# GRLV_double_Rail_v0_2b_P1.net
KiCad netlist of a schematic drawn in Altium Designer
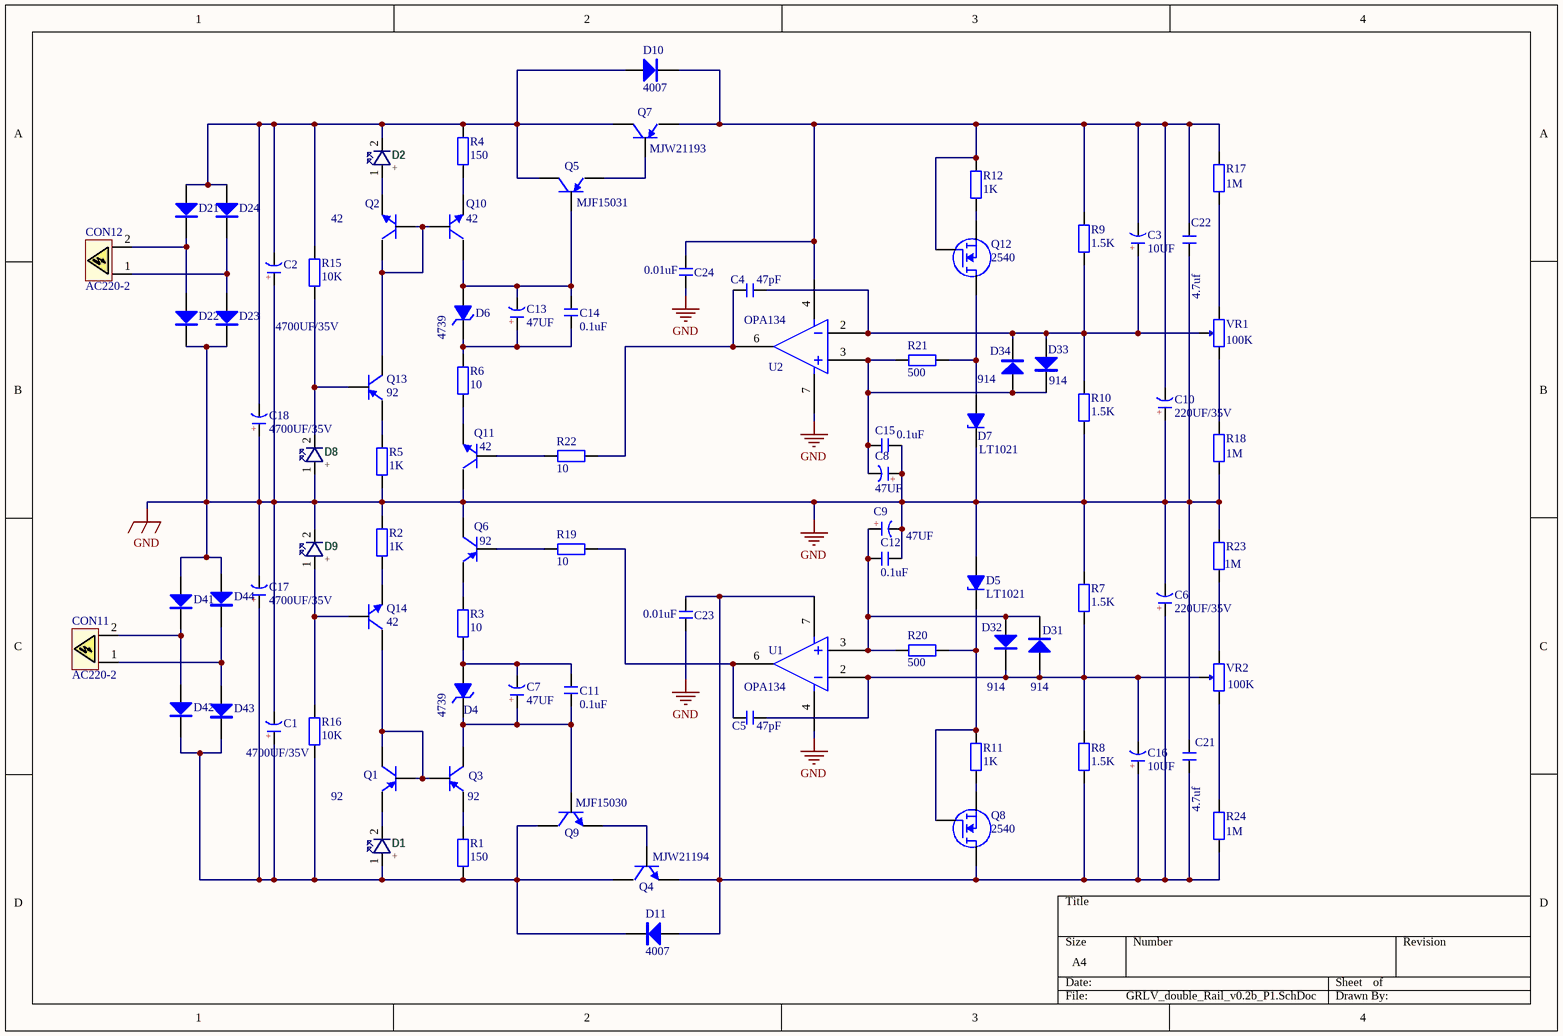
[diagram p0: GRLV_double_Rail_v0.2b_P1.SchDoc]

(export (version "E")
  (design (tool "Eeschema 10.0.6"))
  (components
    (comp (ref "C1")
      (value "4700UF/35V")
      (footprint "CAP 10*22*31.5")
      (description "直插电解电容")
      (fields (field (name "版权归属") "源创客"))
      (libsource (lib "") (part "C-CAP_1"))
    )
    (comp (ref "C2")
      (value "4700UF/35V")
      (footprint "CAP 10*22*31.5")
      (description "直插电解电容")
      (fields (field (name "版权归属") "源创客"))
      (libsource (lib "") (part "C-CAP_1"))
    )
    (comp (ref "C3")
      (value "10UF")
      (footprint "CAP 2.5*6.3*7")
      (description "直插电解电容")
      (fields (field (name "版权归属") "源创客"))
      (libsource (lib "") (part "C-CAP_1"))
    )
    (comp (ref "C4")
      (value "47pF")
      (footprint "CBB 6.3*6.3*5")
      (description "CBB电容")
      (fields (field (name "版权归属") "源创客"))
      (libsource (lib "电阻-电容-电感") (part "C-CBB"))
    )
    (comp (ref "C5")
      (value "47pF")
      (footprint "CBB 6.3*6.3*5")
      (description "CBB电容")
      (fields (field (name "版权归属") "源创客"))
      (libsource (lib "电阻-电容-电感") (part "C-CBB"))
    )
    (comp (ref "C6")
      (value "220UF/35V")
      (footprint "CAP 3.5*8*11.5")
      (description "直插电解电容")
      (fields (field (name "版权归属") "源创客"))
      (libsource (lib "") (part "C-CAP_1"))
    )
    (comp (ref "C7")
      (value "47UF")
      (footprint "CAP 2.5*6.3*11.2")
      (description "直插电解电容")
      (fields (field (name "版权归属") "源创客"))
      (libsource (lib "") (part "C-CAP_1"))
    )
    (comp (ref "C8")
      (value "47UF")
      (footprint "CAP 2.5*6.3*11.2")
      (description "直插电解电容")
      (fields (field (name "版权归属") "源创客"))
      (libsource (lib "电阻-电容-电感") (part "C-CAP"))
    )
    (comp (ref "C9")
      (value "47UF")
      (footprint "CAP 2.5*6.3*11.2")
      (description "直插电解电容")
      (fields (field (name "版权归属") "源创客"))
      (libsource (lib "电阻-电容-电感") (part "C-CAP"))
    )
    (comp (ref "C10")
      (value "220UF/35V")
      (footprint "CAP 3.5*8*11.5")
      (description "直插电解电容")
      (fields (field (name "版权归属") "源创客"))
      (libsource (lib "") (part "C-CAP_1"))
    )
    (comp (ref "C11")
      (value "0.1uF")
      (footprint "CBB 6.3*6.3*5")
      (description "CBB电容")
      (fields (field (name "版权归属") "源创客"))
      (libsource (lib "电阻-电容-电感") (part "C-CBB"))
    )
    (comp (ref "C12")
      (value "0.1uF")
      (footprint "CBB 6.3*6.3*5")
      (description "CBB电容")
      (fields (field (name "版权归属") "源创客"))
      (libsource (lib "电阻-电容-电感") (part "C-CBB"))
    )
    (comp (ref "C13")
      (value "47UF")
      (footprint "CAP 2.5*6.3*11.2")
      (description "直插电解电容")
      (fields (field (name "版权归属") "源创客"))
      (libsource (lib "") (part "C-CAP_1"))
    )
    (comp (ref "C14")
      (value "0.1uF")
      (footprint "CBB 6.3*6.3*5")
      (description "CBB电容")
      (fields (field (name "版权归属") "源创客"))
      (libsource (lib "电阻-电容-电感") (part "C-CBB"))
    )
    (comp (ref "C15")
      (value "0.1uF")
      (footprint "CBB 6.3*6.3*5")
      (description "CBB电容")
      (fields (field (name "版权归属") "源创客"))
      (libsource (lib "电阻-电容-电感") (part "C-CBB"))
    )
    (comp (ref "C16")
      (value "10UF")
      (footprint "CAP 2.5*6.3*7")
      (description "直插电解电容")
      (fields (field (name "版权归属") "源创客"))
      (libsource (lib "") (part "C-CAP_1"))
    )
    (comp (ref "C17")
      (value "4700UF/35V")
      (footprint "CAP 10*22*31.5")
      (description "直插电解电容")
      (fields (field (name "版权归属") "源创客"))
      (libsource (lib "") (part "C-CAP_1"))
    )
    (comp (ref "C18")
      (value "4700UF/35V")
      (footprint "CAP 10*22*31.5")
      (description "直插电解电容")
      (fields (field (name "版权归属") "源创客"))
      (libsource (lib "") (part "C-CAP_1"))
    )
    (comp (ref "C21")
      (value "4.7uf")
      (footprint "CBB 7.2*7.2*13")
      (description "MKS薄膜电容")
      (libsource (lib "电阻-电容-电感") (part "C-MKS"))
    )
    (comp (ref "C22")
      (value "4.7uf")
      (footprint "CBB 7.2*7.2*13")
      (description "MKS薄膜电容")
      (libsource (lib "电阻-电容-电感") (part "C-MKS"))
    )
    (comp (ref "C23")
      (value "0.01uF")
      (footprint "CBB 6.3*6.3*5")
      (description "CBB电容")
      (fields (field (name "Comment") ".01") (field (name "版权归属") "源创客"))
      (libsource (lib "电阻-电容-电感") (part "C-CBB"))
    )
    (comp (ref "C24")
      (value "0.01uF")
      (footprint "CBB 6.3*6.3*5")
      (description "CBB电容")
      (fields (field (name "Comment") ".01") (field (name "版权归属") "源创客"))
      (libsource (lib "电阻-电容-电感") (part "C-CBB"))
    )
    (comp (ref "CON11")
      (value "AC220-2")
      (footprint "HX4.0-2XS")
      (libsource (lib "Connectors") (part "AC220-2"))
    )
    (comp (ref "CON12")
      (value "AC220-2")
      (footprint "HX4.0-2XS")
      (libsource (lib "Connectors") (part "AC220-2"))
    )
    (comp (ref "D1")
      (value "+")
      (footprint "LED 3MM-R")
      (description "直插式LED")
      (libsource (lib "LED") (part "LED"))
    )
    (comp (ref "D2")
      (value "+")
      (footprint "LED 3MM-R")
      (description "直插式LED")
      (libsource (lib "LED") (part "LED"))
    )
    (comp (ref "D4")
      (value "4739")
      (footprint "DO-41")
      (description "9.1V/1W稳压管")
      (libsource (lib "二极管-整流桥") (part "1N4739"))
    )
    (comp (ref "D5")
      (value "LT1021")
      (footprint "DIP8-300_MH")
      (description "10V Precision Reference 2 Pin Config")
      (libsource (lib "电压参考") (part "LT1021-10-2P"))
    )
    (comp (ref "D6")
      (value "4739")
      (footprint "DO-41")
      (description "9.1V/1W稳压管")
      (libsource (lib "二极管-整流桥") (part "1N4739"))
    )
    (comp (ref "D7")
      (value "LT1021")
      (footprint "DIP8-300_MH")
      (description "10V Precision Reference 2 Pin Config")
      (libsource (lib "电压参考") (part "LT1021-10-2P"))
    )
    (comp (ref "D8")
      (value "+")
      (footprint "LED 3MM-R")
      (description "直插式LED")
      (libsource (lib "LED") (part "LED"))
    )
    (comp (ref "D9")
      (value "+")
      (footprint "LED 3MM-R")
      (description "直插式LED")
      (libsource (lib "LED") (part "LED"))
    )
    (comp (ref "D10")
      (value "4007")
      (footprint "DO-41")
      (description "整流二极管")
      (fields (field (name "版权归属") "源创客"))
      (libsource (lib "二极管-整流桥") (part "1N4007"))
    )
    (comp (ref "D11")
      (value "4007")
      (footprint "DO-41")
      (description "整流二极管")
      (fields (field (name "版权归属") "源创客"))
      (libsource (lib "二极管-整流桥") (part "1N4007"))
    )
    (comp (ref "D21")
      (value "VS-HFA08TB60-M3")
      (footprint "DO-15")
      (description "Ultrafast Soft Recovery Diado 8A 600V")
      (libsource (lib "二极管-整流桥") (part "VS-HFA08TB60-M3"))
    )
    (comp (ref "D22")
      (value "VS-HFA08TB60-M3")
      (footprint "DO-15")
      (description "Ultrafast Soft Recovery Diado 8A 600V")
      (libsource (lib "二极管-整流桥") (part "VS-HFA08TB60-M3"))
    )
    (comp (ref "D23")
      (value "VS-HFA08TB60-M3")
      (footprint "DO-15")
      (description "Ultrafast Soft Recovery Diado 8A 600V")
      (libsource (lib "二极管-整流桥") (part "VS-HFA08TB60-M3"))
    )
    (comp (ref "D24")
      (value "VS-HFA08TB60-M3")
      (footprint "DO-15")
      (description "Ultrafast Soft Recovery Diado 8A 600V")
      (libsource (lib "二极管-整流桥") (part "VS-HFA08TB60-M3"))
    )
    (comp (ref "D31")
      (value "914")
      (footprint "DO-35")
      (description "高速开关管 1V/0.25W")
      (libsource (lib "二极管-整流桥") (part "1N914"))
    )
    (comp (ref "D32")
      (value "914")
      (footprint "DO-35")
      (description "高速开关管 1V/0.25W")
      (libsource (lib "二极管-整流桥") (part "1N914"))
    )
    (comp (ref "D33")
      (value "914")
      (footprint "DO-35")
      (description "高速开关管 1V/0.25W")
      (libsource (lib "二极管-整流桥") (part "1N914"))
    )
    (comp (ref "D34")
      (value "914")
      (footprint "DO-35")
      (description "高速开关管 1V/0.25W")
      (libsource (lib "二极管-整流桥") (part "1N914"))
    )
    (comp (ref "D41")
      (value "VS-HFA08TB60-M3")
      (footprint "DO-15")
      (description "Ultrafast Soft Recovery Diado 8A 600V")
      (libsource (lib "二极管-整流桥") (part "VS-HFA08TB60-M3"))
    )
    (comp (ref "D42")
      (value "VS-HFA08TB60-M3")
      (footprint "DO-15")
      (description "Ultrafast Soft Recovery Diado 8A 600V")
      (libsource (lib "二极管-整流桥") (part "VS-HFA08TB60-M3"))
    )
    (comp (ref "D43")
      (value "VS-HFA08TB60-M3")
      (footprint "DO-15")
      (description "Ultrafast Soft Recovery Diado 8A 600V")
      (libsource (lib "二极管-整流桥") (part "VS-HFA08TB60-M3"))
    )
    (comp (ref "D44")
      (value "VS-HFA08TB60-M3")
      (footprint "DO-15")
      (description "Ultrafast Soft Recovery Diado 8A 600V")
      (libsource (lib "二极管-整流桥") (part "VS-HFA08TB60-M3"))
    )
    (comp (ref "Q1")
      (value "92")
      (footprint "TO92A")
      (description "High Voltage PNP Transistor")
      (libsource (lib "三极管") (part "KSP92/93"))
    )
    (comp (ref "Q2")
      (value "42")
      (footprint "TO92A")
      (description "High Voltage NPN Transistor")
      (libsource (lib "三极管") (part "KSP42/43"))
    )
    (comp (ref "Q3")
      (value "92")
      (footprint "TO92A")
      (description "High Voltage PNP Transistor")
      (libsource (lib "三极管") (part "KSP92/93"))
    )
    (comp (ref "Q4")
      (value "MJW21194")
      (footprint "TO247V")
      (description "Power NPN Transistor")
      (libsource (lib "三极管") (part "MJW21194"))
    )
    (comp (ref "Q5")
      (value "MJF15031")
      (footprint "TO220V")
      (description "Power PNP Transistor")
      (libsource (lib "三极管") (part "MJF15031"))
    )
    (comp (ref "Q6")
      (value "92")
      (footprint "TO92A")
      (description "High Voltage PNP Transistor")
      (libsource (lib "三极管") (part "KSP92/93"))
    )
    (comp (ref "Q7")
      (value "MJW21193")
      (footprint "TO247V")
      (description "Power PNP Transistor")
      (libsource (lib "三极管") (part "MJW21193"))
    )
    (comp (ref "Q8")
      (value "2540")
      (footprint "TO92A")
      (description "N沟道耗尽型DMOS场效应管 400V/150ma")
      (libsource (lib "场效应管") (part "DN2540"))
    )
    (comp (ref "Q9")
      (value "MJF15030")
      (footprint "TO220V")
      (description "Power NPN Transistor")
      (libsource (lib "三极管") (part "MJF15030"))
    )
    (comp (ref "Q10")
      (value "42")
      (footprint "TO92A")
      (description "High Voltage NPN Transistor")
      (libsource (lib "三极管") (part "KSP42/43"))
    )
    (comp (ref "Q11")
      (value "42")
      (footprint "TO92A")
      (description "High Voltage NPN Transistor")
      (libsource (lib "三极管") (part "KSP42/43"))
    )
    (comp (ref "Q12")
      (value "2540")
      (footprint "TO92A")
      (description "N沟道耗尽型DMOS场效应管 400V/150ma")
      (libsource (lib "场效应管") (part "DN2540"))
    )
    (comp (ref "Q13")
      (value "92")
      (footprint "TO92A")
      (description "High Voltage PNP Transistor")
      (libsource (lib "三极管") (part "KSP92/93"))
    )
    (comp (ref "Q14")
      (value "42")
      (footprint "TO92A")
      (description "High Voltage NPN Transistor")
      (libsource (lib "三极管") (part "KSP42/43"))
    )
    (comp (ref "R1")
      (value "150")
      (footprint "RS 1/4W")
      (description "直插色环电阻")
      (fields (field (name "版权归属") "源创客"))
      (libsource (lib "电阻-电容-电感") (part "R-CRR"))
    )
    (comp (ref "R2")
      (value "1K")
      (footprint "RS 1/4W")
      (description "直插色环电阻")
      (fields (field (name "版权归属") "源创客"))
      (libsource (lib "电阻-电容-电感") (part "R-CRR"))
    )
    (comp (ref "R3")
      (value "10")
      (footprint "RS 1/4W")
      (description "直插色环电阻")
      (fields (field (name "版权归属") "源创客"))
      (libsource (lib "电阻-电容-电感") (part "R-CRR"))
    )
    (comp (ref "R4")
      (value "150")
      (footprint "RS 1/4W")
      (description "直插色环电阻")
      (fields (field (name "版权归属") "源创客"))
      (libsource (lib "电阻-电容-电感") (part "R-CRR"))
    )
    (comp (ref "R5")
      (value "1K")
      (footprint "RS 1/4W")
      (description "直插色环电阻")
      (fields (field (name "版权归属") "源创客"))
      (libsource (lib "电阻-电容-电感") (part "R-CRR"))
    )
    (comp (ref "R6")
      (value "10")
      (footprint "RS 1/4W")
      (description "直插色环电阻")
      (fields (field (name "版权归属") "源创客"))
      (libsource (lib "电阻-电容-电感") (part "R-CRR"))
    )
    (comp (ref "R7")
      (value "1.5K")
      (footprint "RS 1/4W")
      (description "直插色环电阻")
      (fields (field (name "版权归属") "源创客"))
      (libsource (lib "电阻-电容-电感") (part "R-CRR"))
    )
    (comp (ref "R8")
      (value "1.5K")
      (footprint "RS 1/4W")
      (description "直插色环电阻")
      (fields (field (name "版权归属") "源创客"))
      (libsource (lib "电阻-电容-电感") (part "R-CRR"))
    )
    (comp (ref "R9")
      (value "1.5K")
      (footprint "RS 1/4W")
      (description "直插色环电阻")
      (fields (field (name "版权归属") "源创客"))
      (libsource (lib "电阻-电容-电感") (part "R-CRR"))
    )
    (comp (ref "R10")
      (value "1.5K")
      (footprint "RS 1/4W")
      (description "直插色环电阻")
      (fields (field (name "版权归属") "源创客"))
      (libsource (lib "电阻-电容-电感") (part "R-CRR"))
    )
    (comp (ref "R11")
      (value "1K")
      (footprint "RS 1/4W")
      (description "直插色环电阻")
      (fields (field (name "版权归属") "源创客"))
      (libsource (lib "电阻-电容-电感") (part "R-CRR"))
    )
    (comp (ref "R12")
      (value "1K")
      (footprint "RS 1/4W")
      (description "直插色环电阻")
      (fields (field (name "版权归属") "源创客"))
      (libsource (lib "电阻-电容-电感") (part "R-CRR"))
    )
    (comp (ref "R15")
      (value "10K")
      (footprint "RS 1/4W")
      (description "直插色环电阻")
      (fields (field (name "版权归属") "源创客"))
      (libsource (lib "电阻-电容-电感") (part "R-CRR"))
    )
    (comp (ref "R16")
      (value "10K")
      (footprint "RS 1/4W")
      (description "直插色环电阻")
      (fields (field (name "版权归属") "源创客"))
      (libsource (lib "电阻-电容-电感") (part "R-CRR"))
    )
    (comp (ref "R17")
      (value "1M")
      (footprint "RS 1/4W")
      (description "直插色环电阻")
      (fields (field (name "版权归属") "源创客"))
      (libsource (lib "电阻-电容-电感") (part "R-CRR"))
    )
    (comp (ref "R18")
      (value "1M")
      (footprint "RS 1/4W")
      (description "直插色环电阻")
      (fields (field (name "版权归属") "源创客"))
      (libsource (lib "电阻-电容-电感") (part "R-CRR"))
    )
    (comp (ref "R19")
      (value "10")
      (footprint "RS 1/4W")
      (description "直插色环电阻")
      (fields (field (name "版权归属") "源创客"))
      (libsource (lib "电阻-电容-电感") (part "R-CRR"))
    )
    (comp (ref "R20")
      (value "500")
      (footprint "RS 1/4W")
      (description "直插色环电阻")
      (fields (field (name "版权归属") "源创客"))
      (libsource (lib "电阻-电容-电感") (part "R-CRR"))
    )
    (comp (ref "R21")
      (value "500")
      (footprint "RS 1/4W")
      (description "直插色环电阻")
      (fields (field (name "版权归属") "源创客"))
      (libsource (lib "电阻-电容-电感") (part "R-CRR"))
    )
    (comp (ref "R22")
      (value "10")
      (footprint "RS 1/4W")
      (description "直插色环电阻")
      (fields (field (name "版权归属") "源创客"))
      (libsource (lib "电阻-电容-电感") (part "R-CRR"))
    )
    (comp (ref "R23")
      (value "1M")
      (footprint "RS 1/4W")
      (description "直插色环电阻")
      (fields (field (name "版权归属") "源创客"))
      (libsource (lib "电阻-电容-电感") (part "R-CRR"))
    )
    (comp (ref "R24")
      (value "1M")
      (footprint "RS 1/4W")
      (description "直插色环电阻")
      (fields (field (name "版权归属") "源创客"))
      (libsource (lib "电阻-电容-电感") (part "R-CRR"))
    )
    (comp (ref "U1") (value "OPA134") (footprint "DIP8-300_MH") (libsource (lib "运放") (part "OPA134PA")))
    (comp (ref "U2") (value "OPA134") (footprint "DIP8-300_MH") (libsource (lib "运放") (part "OPA134PA")))
    (comp (ref "VR1")
      (value "100K")
      (footprint "RS 1/2W-VR")
      (description "直插可调电阻-顶调")
      (libsource (lib "电阻-电容-电感") (part "VR-W"))
    )
    (comp (ref "VR2")
      (value "100K")
      (footprint "RS 1/2W-VR")
      (description "直插可调电阻-顶调")
      (libsource (lib "电阻-电容-电感") (part "VR-W"))
    )
  )
  (nets
    (net (code "1") (name "GND") (class "Default")
      (node (ref "C1") (pin "2") (pinfunction "K_2") (pintype "passive"))
      (node (ref "C10") (pin "1") (pinfunction "A_1") (pintype "passive"))
      (node (ref "C12") (pin "2") (pinfunction "2_2") (pintype "passive"))
      (node (ref "C15") (pin "2") (pinfunction "2_2") (pintype "passive"))
      (node (ref "C17") (pin "2") (pinfunction "K_2") (pintype "passive"))
      (node (ref "C18") (pin "1") (pinfunction "A_1") (pintype "passive"))
      (node (ref "C2") (pin "1") (pinfunction "A_1") (pintype "passive"))
      (node (ref "C21") (pin "2") (pinfunction "2_2") (pintype "passive"))
      (node (ref "C22") (pin "1") (pinfunction "1_1") (pintype "passive"))
      (node (ref "C23") (pin "1") (pinfunction "1_1") (pintype "passive"))
      (node (ref "C24") (pin "1") (pinfunction "1_1") (pintype "passive"))
      (node (ref "C6") (pin "2") (pinfunction "K_2") (pintype "passive"))
      (node (ref "C8") (pin "1") (pinfunction "A_1") (pintype "passive"))
      (node (ref "C9") (pin "2") (pinfunction "K_2") (pintype "passive"))
      (node (ref "D22") (pin "1") (pinfunction "Cathode_1") (pintype "passive"))
      (node (ref "D23") (pin "1") (pinfunction "Cathode_1") (pintype "passive"))
      (node (ref "D41") (pin "2") (pinfunction "Anode_2") (pintype "passive"))
      (node (ref "D44") (pin "2") (pinfunction "Anode_2") (pintype "passive"))
      (node (ref "D5") (pin "4") (pinfunction "A_4") (pintype "passive"))
      (node (ref "D7") (pin "6") (pinfunction "K_6") (pintype "passive"))
      (node (ref "D8") (pin "1") (pinfunction "A_1") (pintype "passive"))
      (node (ref "D9") (pin "2") (pinfunction "K_2") (pintype "passive"))
      (node (ref "Q11") (pin "3") (pinfunction "C_3") (pintype "passive"))
      (node (ref "Q6") (pin "3") (pinfunction "C_3") (pintype "passive"))
      (node (ref "R10") (pin "1") (pinfunction "1_1") (pintype "passive"))
      (node (ref "R18") (pin "1") (pinfunction "1_1") (pintype "passive"))
      (node (ref "R2") (pin "2") (pinfunction "2_2") (pintype "passive"))
      (node (ref "R23") (pin "2") (pinfunction "2_2") (pintype "passive"))
      (node (ref "R5") (pin "1") (pinfunction "1_1") (pintype "passive"))
      (node (ref "R7") (pin "2") (pinfunction "2_2") (pintype "passive"))
      (node (ref "U1") (pin "4") (pinfunction "V-_4") (pintype "passive"))
      (node (ref "U2") (pin "7") (pinfunction "V+_7") (pintype "passive"))
    )
    (net (code "2") (name "Net-(C1-A)") (class "Default")
      (node (ref "C1") (pin "1") (pinfunction "A_1") (pintype "passive"))
      (node (ref "C17") (pin "1") (pinfunction "A_1") (pintype "passive"))
      (node (ref "D1") (pin "1") (pinfunction "A_1") (pintype "passive"))
      (node (ref "D11") (pin "2") (pinfunction "K_2") (pintype "passive"))
      (node (ref "D42") (pin "1") (pinfunction "Cathode_1") (pintype "passive"))
      (node (ref "D43") (pin "1") (pinfunction "Cathode_1") (pintype "passive"))
      (node (ref "Q4") (pin "2") (pinfunction "C_2") (pintype "passive"))
      (node (ref "Q9") (pin "2") (pinfunction "C_2") (pintype "passive"))
      (node (ref "R1") (pin "1") (pinfunction "1_1") (pintype "passive"))
      (node (ref "R16") (pin "1") (pinfunction "1_1") (pintype "passive"))
    )
    (net (code "3") (name "Net-(C3-A)") (class "Default")
      (node (ref "C3") (pin "1") (pinfunction "A_1") (pintype "passive"))
      (node (ref "C4") (pin "2") (pinfunction "2_2") (pintype "passive"))
      (node (ref "D33") (pin "1") (pinfunction "A_1") (pintype "passive"))
      (node (ref "D34") (pin "2") (pinfunction "K_2") (pintype "passive"))
      (node (ref "R10") (pin "2") (pinfunction "2_2") (pintype "passive"))
      (node (ref "R9") (pin "1") (pinfunction "1_1") (pintype "passive"))
      (node (ref "U2") (pin "2") (pinfunction "-in_2") (pintype "passive"))
      (node (ref "VR1") (pin "3") (pinfunction "3_3") (pintype "passive"))
    )
    (net (code "4") (name "Net-(C7-A)") (class "Default")
      (node (ref "C11") (pin "1") (pinfunction "1_1") (pintype "passive"))
      (node (ref "C7") (pin "1") (pinfunction "A_1") (pintype "passive"))
      (node (ref "D4") (pin "2") (pinfunction "K_2") (pintype "passive"))
      (node (ref "Q3") (pin "3") (pinfunction "C_3") (pintype "passive"))
      (node (ref "Q9") (pin "1") (pinfunction "B_1") (pintype "passive"))
    )
    (net (code "5") (name "Net-(C7-K)") (class "Default")
      (node (ref "C11") (pin "2") (pinfunction "2_2") (pintype "passive"))
      (node (ref "C7") (pin "2") (pinfunction "K_2") (pintype "passive"))
      (node (ref "D4") (pin "1") (pinfunction "A_1") (pintype "passive"))
      (node (ref "R3") (pin "1") (pinfunction "1_1") (pintype "passive"))
    )
    (net (code "6") (name "Net-(C8-K)") (class "Default")
      (node (ref "C15") (pin "1") (pinfunction "1_1") (pintype "passive"))
      (node (ref "C8") (pin "2") (pinfunction "K_2") (pintype "passive"))
      (node (ref "D33") (pin "2") (pinfunction "K_2") (pintype "passive"))
      (node (ref "D34") (pin "1") (pinfunction "A_1") (pintype "passive"))
      (node (ref "R21") (pin "1") (pinfunction "1_1") (pintype "passive"))
      (node (ref "U2") (pin "3") (pinfunction "+in_3") (pintype "passive"))
    )
    (net (code "7") (name "Net-(C9-A)") (class "Default")
      (node (ref "C12") (pin "1") (pinfunction "1_1") (pintype "passive"))
      (node (ref "C9") (pin "1") (pinfunction "A_1") (pintype "passive"))
      (node (ref "D31") (pin "2") (pinfunction "K_2") (pintype "passive"))
      (node (ref "D32") (pin "1") (pinfunction "A_1") (pintype "passive"))
      (node (ref "R20") (pin "1") (pinfunction "1_1") (pintype "passive"))
      (node (ref "U1") (pin "3") (pinfunction "+in_3") (pintype "passive"))
    )
    (net (code "8") (name "Net-(C10-K)") (class "Default")
      (node (ref "C10") (pin "2") (pinfunction "K_2") (pintype "passive"))
      (node (ref "C22") (pin "2") (pinfunction "2_2") (pintype "passive"))
      (node (ref "C24") (pin "2") (pinfunction "2_2") (pintype "passive"))
      (node (ref "C3") (pin "2") (pinfunction "K_2") (pintype "passive"))
      (node (ref "D10") (pin "2") (pinfunction "K_2") (pintype "passive"))
      (node (ref "Q12") (pin "2") (pinfunction "G_2") (pintype "passive"))
      (node (ref "Q7") (pin "3") (pinfunction "E_3") (pintype "passive"))
      (node (ref "R12") (pin "2") (pinfunction "2_2") (pintype "passive"))
      (node (ref "R17") (pin "2") (pinfunction "2_2") (pintype "passive"))
      (node (ref "R9") (pin "2") (pinfunction "2_2") (pintype "passive"))
      (node (ref "U2") (pin "4") (pinfunction "V-_4") (pintype "passive"))
    )
    (net (code "9") (name "Net-(C13-A)") (class "Default")
      (node (ref "C13") (pin "1") (pinfunction "A_1") (pintype "passive"))
      (node (ref "C14") (pin "1") (pinfunction "1_1") (pintype "passive"))
      (node (ref "D6") (pin "2") (pinfunction "K_2") (pintype "passive"))
      (node (ref "R6") (pin "2") (pinfunction "2_2") (pintype "passive"))
    )
    (net (code "10") (name "Net-(C13-K)") (class "Default")
      (node (ref "C13") (pin "2") (pinfunction "K_2") (pintype "passive"))
      (node (ref "C14") (pin "2") (pinfunction "2_2") (pintype "passive"))
      (node (ref "D6") (pin "1") (pinfunction "A_1") (pintype "passive"))
      (node (ref "Q10") (pin "3") (pinfunction "C_3") (pintype "passive"))
      (node (ref "Q5") (pin "1") (pinfunction "B_1") (pintype "passive"))
    )
    (net (code "11") (name "Net-(C16-A)") (class "Default")
      (node (ref "C16") (pin "1") (pinfunction "A_1") (pintype "passive"))
      (node (ref "C21") (pin "1") (pinfunction "1_1") (pintype "passive"))
      (node (ref "C23") (pin "2") (pinfunction "2_2") (pintype "passive"))
      (node (ref "C6") (pin "1") (pinfunction "A_1") (pintype "passive"))
      (node (ref "D11") (pin "1") (pinfunction "A_1") (pintype "passive"))
      (node (ref "Q4") (pin "3") (pinfunction "E_3") (pintype "passive"))
      (node (ref "Q8") (pin "3") (pinfunction "D_3") (pintype "passive"))
      (node (ref "R24") (pin "1") (pinfunction "1_1") (pintype "passive"))
      (node (ref "R8") (pin "1") (pinfunction "1_1") (pintype "passive"))
      (node (ref "U1") (pin "7") (pinfunction "V+_7") (pintype "passive"))
    )
    (net (code "12") (name "Net-(C16-K)") (class "Default")
      (node (ref "C16") (pin "2") (pinfunction "K_2") (pintype "passive"))
      (node (ref "C5") (pin "2") (pinfunction "2_2") (pintype "passive"))
      (node (ref "D31") (pin "1") (pinfunction "A_1") (pintype "passive"))
      (node (ref "D32") (pin "2") (pinfunction "K_2") (pintype "passive"))
      (node (ref "R7") (pin "1") (pinfunction "1_1") (pintype "passive"))
      (node (ref "R8") (pin "2") (pinfunction "2_2") (pintype "passive"))
      (node (ref "U1") (pin "2") (pinfunction "-in_2") (pintype "passive"))
      (node (ref "VR2") (pin "3") (pinfunction "3_3") (pintype "passive"))
    )
    (net (code "13") (name "Net-(C18-K)") (class "Default")
      (node (ref "C18") (pin "2") (pinfunction "K_2") (pintype "passive"))
      (node (ref "C2") (pin "2") (pinfunction "K_2") (pintype "passive"))
      (node (ref "D10") (pin "1") (pinfunction "A_1") (pintype "passive"))
      (node (ref "D2") (pin "2") (pinfunction "K_2") (pintype "passive"))
      (node (ref "D21") (pin "2") (pinfunction "Anode_2") (pintype "passive"))
      (node (ref "D24") (pin "2") (pinfunction "Anode_2") (pintype "passive"))
      (node (ref "Q5") (pin "2") (pinfunction "C_2") (pintype "passive"))
      (node (ref "Q7") (pin "2") (pinfunction "C_2") (pintype "passive"))
      (node (ref "R15") (pin "2") (pinfunction "2_2") (pintype "passive"))
      (node (ref "R4") (pin "2") (pinfunction "2_2") (pintype "passive"))
    )
    (net (code "14") (name "Net-(CON11-G)") (class "Default")
      (node (ref "CON11") (pin "2") (pinfunction "G_2") (pintype "passive"))
      (node (ref "D41") (pin "1") (pinfunction "Cathode_1") (pintype "passive"))
      (node (ref "D42") (pin "2") (pinfunction "Anode_2") (pintype "passive"))
    )
    (net (code "15") (name "Net-(CON11-L)") (class "Default")
      (node (ref "CON11") (pin "1") (pinfunction "L_1") (pintype "passive"))
      (node (ref "D43") (pin "2") (pinfunction "Anode_2") (pintype "passive"))
      (node (ref "D44") (pin "1") (pinfunction "Cathode_1") (pintype "passive"))
    )
    (net (code "16") (name "Net-(CON12-G)") (class "Default")
      (node (ref "CON12") (pin "2") (pinfunction "G_2") (pintype "passive"))
      (node (ref "D21") (pin "1") (pinfunction "Cathode_1") (pintype "passive"))
      (node (ref "D22") (pin "2") (pinfunction "Anode_2") (pintype "passive"))
    )
    (net (code "17") (name "Net-(CON12-L)") (class "Default")
      (node (ref "CON12") (pin "1") (pinfunction "L_1") (pintype "passive"))
      (node (ref "D23") (pin "2") (pinfunction "Anode_2") (pintype "passive"))
      (node (ref "D24") (pin "1") (pinfunction "Cathode_1") (pintype "passive"))
    )
    (net (code "18") (name "Net-(D1-K)") (class "Default")
      (node (ref "D1") (pin "2") (pinfunction "K_2") (pintype "passive"))
      (node (ref "Q1") (pin "1") (pinfunction "E_1") (pintype "passive"))
    )
    (net (code "19") (name "Net-(D2-A)") (class "Default")
      (node (ref "D2") (pin "1") (pinfunction "A_1") (pintype "passive"))
      (node (ref "Q2") (pin "1") (pinfunction "E_1") (pintype "passive"))
    )
    (net (code "20") (name "Net-(D5-K)") (class "Default")
      (node (ref "D5") (pin "6") (pinfunction "K_6") (pintype "passive"))
      (node (ref "Q8") (pin "2") (pinfunction "G_2") (pintype "passive"))
      (node (ref "R11") (pin "2") (pinfunction "2_2") (pintype "passive"))
      (node (ref "R20") (pin "2") (pinfunction "2_2") (pintype "passive"))
    )
    (net (code "21") (name "Net-(D7-A)") (class "Default")
      (node (ref "D7") (pin "4") (pinfunction "A_4") (pintype "passive"))
      (node (ref "Q12") (pin "3") (pinfunction "D_3") (pintype "passive"))
      (node (ref "R21") (pin "2") (pinfunction "2_2") (pintype "passive"))
    )
    (net (code "22") (name "Net-(D8-K)") (class "Default")
      (node (ref "D8") (pin "2") (pinfunction "K_2") (pintype "passive"))
      (node (ref "Q13") (pin "2") (pinfunction "B_2") (pintype "passive"))
      (node (ref "R15") (pin "1") (pinfunction "1_1") (pintype "passive"))
    )
    (net (code "23") (name "Net-(D9-A)") (class "Default")
      (node (ref "D9") (pin "1") (pinfunction "A_1") (pintype "passive"))
      (node (ref "Q14") (pin "2") (pinfunction "B_2") (pintype "passive"))
      (node (ref "R16") (pin "2") (pinfunction "2_2") (pintype "passive"))
    )
    (net (code "24") (name "Net-(Q1-B)") (class "Default")
      (node (ref "Q1") (pin "2") (pinfunction "B_2") (pintype "passive"))
      (node (ref "Q1") (pin "3") (pinfunction "C_3") (pintype "passive"))
      (node (ref "Q14") (pin "3") (pinfunction "C_3") (pintype "passive"))
      (node (ref "Q3") (pin "2") (pinfunction "B_2") (pintype "passive"))
    )
    (net (code "25") (name "Net-(Q3-E)") (class "Default")
      (node (ref "Q3") (pin "1") (pinfunction "E_1") (pintype "passive"))
      (node (ref "R1") (pin "2") (pinfunction "2_2") (pintype "passive"))
    )
    (net (code "26") (name "Net-(Q4-B)") (class "Default")
      (node (ref "Q4") (pin "1") (pinfunction "B_1") (pintype "passive"))
      (node (ref "Q9") (pin "3") (pinfunction "E_3") (pintype "passive"))
    )
    (net (code "27") (name "Net-(Q5-E)") (class "Default")
      (node (ref "Q5") (pin "3") (pinfunction "E_3") (pintype "passive"))
      (node (ref "Q7") (pin "1") (pinfunction "B_1") (pintype "passive"))
    )
    (net (code "28") (name "Net-(Q6-B)") (class "Default")
      (node (ref "Q6") (pin "2") (pinfunction "B_2") (pintype "passive"))
      (node (ref "R19") (pin "1") (pinfunction "1_1") (pintype "passive"))
    )
    (net (code "29") (name "Net-(Q6-E)") (class "Default")
      (node (ref "Q6") (pin "1") (pinfunction "E_1") (pintype "passive"))
      (node (ref "R3") (pin "2") (pinfunction "2_2") (pintype "passive"))
    )
    (net (code "30") (name "Net-(Q8-S)") (class "Default")
      (node (ref "Q8") (pin "1") (pinfunction "S_1") (pintype "passive"))
      (node (ref "R11") (pin "1") (pinfunction "1_1") (pintype "passive"))
    )
    (net (code "31") (name "Net-(Q10-B)") (class "Default")
      (node (ref "Q10") (pin "2") (pinfunction "B_2") (pintype "passive"))
      (node (ref "Q13") (pin "3") (pinfunction "C_3") (pintype "passive"))
      (node (ref "Q2") (pin "2") (pinfunction "B_2") (pintype "passive"))
      (node (ref "Q2") (pin "3") (pinfunction "C_3") (pintype "passive"))
    )
    (net (code "32") (name "Net-(Q10-E)") (class "Default")
      (node (ref "Q10") (pin "1") (pinfunction "E_1") (pintype "passive"))
      (node (ref "R4") (pin "1") (pinfunction "1_1") (pintype "passive"))
    )
    (net (code "33") (name "Net-(Q11-B)") (class "Default")
      (node (ref "Q11") (pin "2") (pinfunction "B_2") (pintype "passive"))
      (node (ref "R22") (pin "1") (pinfunction "1_1") (pintype "passive"))
    )
    (net (code "34") (name "Net-(Q11-E)") (class "Default")
      (node (ref "Q11") (pin "1") (pinfunction "E_1") (pintype "passive"))
      (node (ref "R6") (pin "1") (pinfunction "1_1") (pintype "passive"))
    )
    (net (code "35") (name "Net-(Q12-S)") (class "Default")
      (node (ref "Q12") (pin "1") (pinfunction "S_1") (pintype "passive"))
      (node (ref "R12") (pin "1") (pinfunction "1_1") (pintype "passive"))
    )
    (net (code "36") (name "Net-(Q13-E)") (class "Default")
      (node (ref "Q13") (pin "1") (pinfunction "E_1") (pintype "passive"))
      (node (ref "R5") (pin "2") (pinfunction "2_2") (pintype "passive"))
    )
    (net (code "37") (name "Net-(Q14-E)") (class "Default")
      (node (ref "Q14") (pin "1") (pinfunction "E_1") (pintype "passive"))
      (node (ref "R2") (pin "1") (pinfunction "1_1") (pintype "passive"))
    )
    (net (code "38") (name "Net-(R17-Pad1)") (class "Default")
      (node (ref "R17") (pin "1") (pinfunction "1_1") (pintype "passive"))
      (node (ref "VR1") (pin "2") (pinfunction "2_2") (pintype "passive"))
    )
    (net (code "39") (name "Net-(R18-Pad2)") (class "Default")
      (node (ref "R18") (pin "2") (pinfunction "2_2") (pintype "passive"))
      (node (ref "VR1") (pin "1") (pinfunction "1_1") (pintype "passive"))
    )
    (net (code "40") (name "Net-(R23-Pad1)") (class "Default")
      (node (ref "R23") (pin "1") (pinfunction "1_1") (pintype "passive"))
      (node (ref "VR2") (pin "2") (pinfunction "2_2") (pintype "passive"))
    )
    (net (code "41") (name "Net-(R24-Pad2)") (class "Default")
      (node (ref "R24") (pin "2") (pinfunction "2_2") (pintype "passive"))
      (node (ref "VR2") (pin "1") (pinfunction "1_1") (pintype "passive"))
    )
    (net (code "42") (name "Net-(U1-out)") (class "Default")
      (node (ref "C5") (pin "1") (pinfunction "1_1") (pintype "passive"))
      (node (ref "R19") (pin "2") (pinfunction "2_2") (pintype "passive"))
      (node (ref "U1") (pin "6") (pinfunction "out_6") (pintype "passive"))
    )
    (net (code "43") (name "Net-(U2-out)") (class "Default")
      (node (ref "C4") (pin "1") (pinfunction "1_1") (pintype "passive"))
      (node (ref "R22") (pin "2") (pinfunction "2_2") (pintype "passive"))
      (node (ref "U2") (pin "6") (pinfunction "out_6") (pintype "passive"))
    )
  )
)
